# gatorBytes_Sensor_board.net
KiCad netlist of a schematic drawn in EAGLE
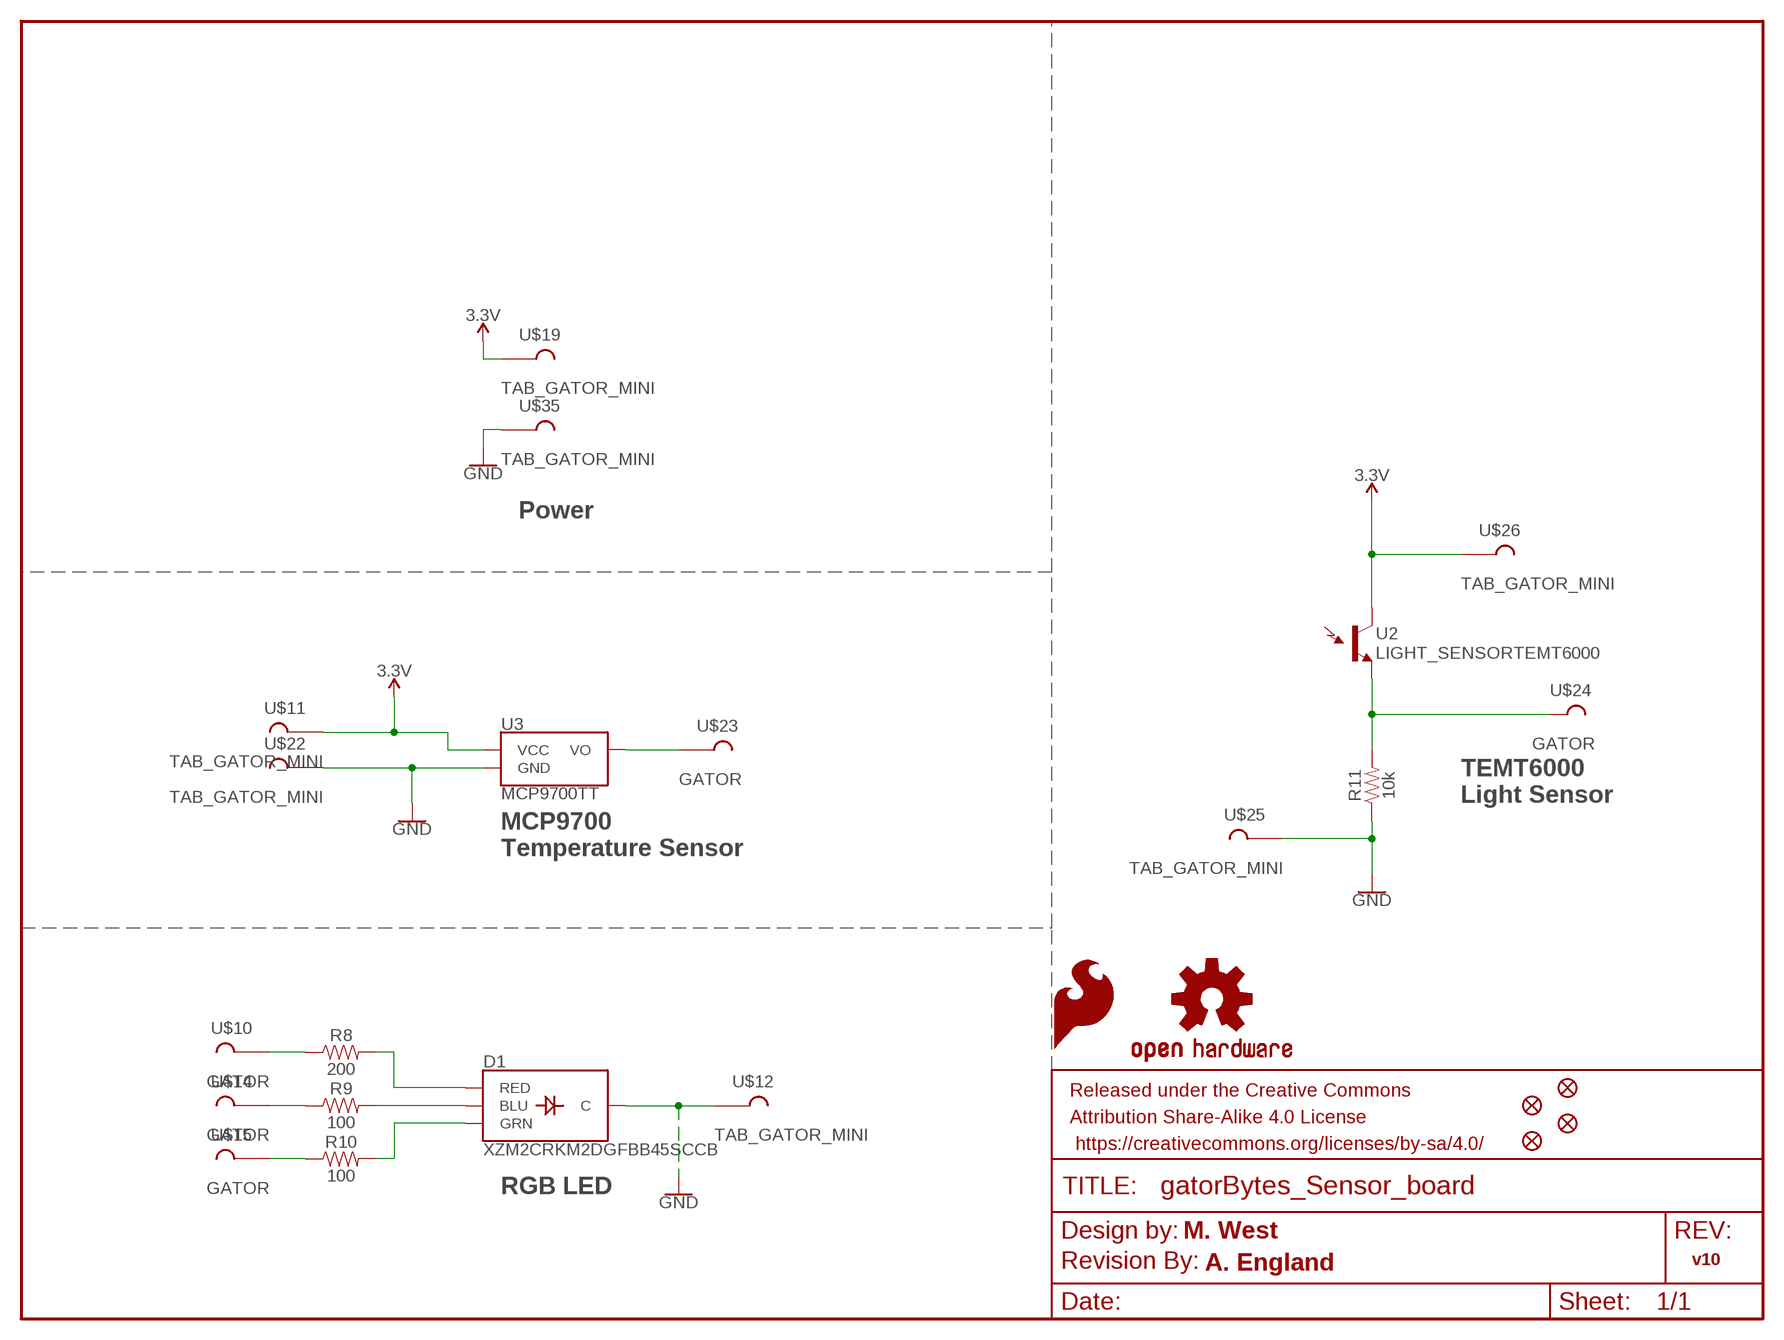
[diagram p0: schematic, sheet 1]

(export (version "E")
  (design (tool "Eeschema 10.0.6"))
  (components
    (comp (ref "D1")
      (value "XZM2CRKM2DGFBB45SCCB")
      (footprint "eagle-import:PLCC4SMDLED")
      (libsource (lib "eagle-import") (part "SUNLEDSMD1"))
    )
    (comp (ref "FD1")
      (value "FIDUCIALUFIDUCIAL")
      (footprint "eagle-import:FIDUCIAL-MICRO")
      (libsource (lib "eagle-import") (part "FIDUCIALUFIDUCIAL"))
    )
    (comp (ref "FD2")
      (value "FIDUCIALUFIDUCIAL")
      (footprint "eagle-import:FIDUCIAL-MICRO")
      (libsource (lib "eagle-import") (part "FIDUCIALUFIDUCIAL"))
    )
    (comp (ref "FD3")
      (value "FIDUCIALUFIDUCIAL")
      (footprint "eagle-import:FIDUCIAL-MICRO")
      (libsource (lib "eagle-import") (part "FIDUCIALUFIDUCIAL"))
    )
    (comp (ref "FD4")
      (value "FIDUCIALUFIDUCIAL")
      (footprint "eagle-import:FIDUCIAL-MICRO")
      (libsource (lib "eagle-import") (part "FIDUCIALUFIDUCIAL"))
    )
    (comp (ref "FRAME1")
      (value "FRAME-LETTER")
      (footprint "eagle-import:CREATIVE_COMMONS")
      (libsource (lib "eagle-import") (part "FRAME-LETTER"))
    )
    (comp (ref "LOGO1")
      (value "SFE_LOGO_FLAME.1_INCH")
      (footprint "eagle-import:SFE_LOGO_FLAME_.1")
      (libsource (lib "eagle-import") (part "SFE_LOGO_FLAME.1_INCH"))
    )
    (comp (ref "LOGO2")
      (value "OSHW-LOGOS")
      (footprint "eagle-import:OSHW-LOGO-S")
      (libsource (lib "eagle-import") (part "OSHW-LOGOS"))
    )
    (comp (ref "LOGO7")
      (value "REVISION")
      (footprint "eagle-import:REVISION")
      (libsource (lib "eagle-import") (part "REVISION"))
    )
    (comp (ref "R8")
      (value "200")
      (footprint "eagle-import:0603")
      (libsource (lib "eagle-import") (part "200OHM-0603-1/10W-1%"))
    )
    (comp (ref "R9")
      (value "100")
      (footprint "eagle-import:0603")
      (libsource (lib "eagle-import") (part "100OHM-0603-1/4W-5%"))
    )
    (comp (ref "R10")
      (value "100")
      (footprint "eagle-import:0603")
      (libsource (lib "eagle-import") (part "100OHM-0603-1/4W-5%"))
    )
    (comp (ref "R11")
      (value "10k")
      (footprint "eagle-import:0603")
      (libsource (lib "eagle-import") (part "10KOHM-0603-1/10W-1%"))
    )
    (comp (ref "U$10")
      (value "GATOR")
      (footprint "eagle-import:GATOR")
      (libsource (lib "eagle-import") (part "GATOR"))
    )
    (comp (ref "U$11")
      (value "TAB_GATOR_MINI")
      (footprint "eagle-import:TAB_GATOR_MINI")
      (libsource (lib "eagle-import") (part "TAB_GATOR_MINI"))
    )
    (comp (ref "U$12")
      (value "TAB_GATOR_MINI")
      (footprint "eagle-import:TAB_GATOR_MINI")
      (libsource (lib "eagle-import") (part "TAB_GATOR_MINI"))
    )
    (comp (ref "U$14")
      (value "GATOR")
      (footprint "eagle-import:GATOR")
      (libsource (lib "eagle-import") (part "GATOR"))
    )
    (comp (ref "U$15")
      (value "GATOR")
      (footprint "eagle-import:GATOR")
      (libsource (lib "eagle-import") (part "GATOR"))
    )
    (comp (ref "U$19")
      (value "TAB_GATOR_MINI")
      (footprint "eagle-import:TAB_GATOR_MINI")
      (libsource (lib "eagle-import") (part "TAB_GATOR_MINI"))
    )
    (comp (ref "U$22")
      (value "TAB_GATOR_MINI")
      (footprint "eagle-import:TAB_GATOR_MINI")
      (libsource (lib "eagle-import") (part "TAB_GATOR_MINI"))
    )
    (comp (ref "U$23")
      (value "GATOR")
      (footprint "eagle-import:GATOR")
      (libsource (lib "eagle-import") (part "GATOR"))
    )
    (comp (ref "U$24")
      (value "GATOR")
      (footprint "eagle-import:GATOR")
      (libsource (lib "eagle-import") (part "GATOR"))
    )
    (comp (ref "U$25")
      (value "TAB_GATOR_MINI")
      (footprint "eagle-import:TAB_GATOR_MINI")
      (libsource (lib "eagle-import") (part "TAB_GATOR_MINI"))
    )
    (comp (ref "U$26")
      (value "TAB_GATOR_MINI")
      (footprint "eagle-import:TAB_GATOR_MINI")
      (libsource (lib "eagle-import") (part "TAB_GATOR_MINI"))
    )
    (comp (ref "U$35")
      (value "TAB_GATOR_MINI")
      (footprint "eagle-import:TAB_GATOR_MINI")
      (libsource (lib "eagle-import") (part "TAB_GATOR_MINI"))
    )
    (comp (ref "U2")
      (value "LIGHT_SENSORTEMT6000")
      (footprint "eagle-import:TEMT6000")
      (libsource (lib "eagle-import") (part "LIGHT_SENSORTEMT6000"))
    )
    (comp (ref "U3")
      (value "MCP9700TT")
      (footprint "eagle-import:SOT23-3")
      (libsource (lib "eagle-import") (part "MCP9700TT"))
    )
  )
  (nets
    (net (code "1") (name "3.3V") (class "Default")
      (node (ref "U$11") (pin "P1") (pinfunction "P$1_P1") (pintype "bidirectional"))
      (node (ref "U$19") (pin "P1") (pinfunction "P$1_P1") (pintype "bidirectional"))
      (node (ref "U$26") (pin "P1") (pinfunction "P$1_P1") (pintype "bidirectional"))
      (node (ref "U2") (pin "COLLECTOR") (pinfunction "C1_COLLECTOR") (pintype "passive"))
      (node (ref "U3") (pin "1") (pinfunction "VCC_1") (pintype "bidirectional"))
    )
    (net (code "2") (name "GND") (class "Default")
      (node (ref "D1") (pin "4") (pinfunction "C_4") (pintype "bidirectional"))
      (node (ref "R11") (pin "1") (pinfunction "1_1") (pintype "passive"))
      (node (ref "U$12") (pin "P1") (pinfunction "P$1_P1") (pintype "bidirectional"))
      (node (ref "U$22") (pin "P1") (pinfunction "P$1_P1") (pintype "bidirectional"))
      (node (ref "U$25") (pin "P1") (pinfunction "P$1_P1") (pintype "bidirectional"))
      (node (ref "U$35") (pin "P1") (pinfunction "P$1_P1") (pintype "bidirectional"))
      (node (ref "U3") (pin "3") (pinfunction "GND_3") (pintype "bidirectional"))
    )
    (net (code "3") (name "Net-(D1-BLU)") (class "Default")
      (node (ref "D1") (pin "3") (pinfunction "BLU_3") (pintype "bidirectional"))
      (node (ref "R9") (pin "2") (pinfunction "2_2") (pintype "passive"))
    )
    (net (code "4") (name "Net-(D1-GRN)") (class "Default")
      (node (ref "D1") (pin "2") (pinfunction "GRN_2") (pintype "bidirectional"))
      (node (ref "R10") (pin "2") (pinfunction "2_2") (pintype "passive"))
    )
    (net (code "5") (name "Net-(D1-RED)") (class "Default")
      (node (ref "D1") (pin "1") (pinfunction "RED_1") (pintype "bidirectional"))
      (node (ref "R8") (pin "2") (pinfunction "2_2") (pintype "passive"))
    )
    (net (code "6") (name "Net-(R8-Pad1)") (class "Default")
      (node (ref "R8") (pin "1") (pinfunction "1_1") (pintype "passive"))
      (node (ref "U$10") (pin "P$1") (pinfunction "P$1_P$1") (pintype "bidirectional"))
      (node (ref "U$10") (pin "P$2") (pinfunction "P$1_P$2") (pintype "bidirectional"))
    )
    (net (code "7") (name "Net-(R9-Pad1)") (class "Default")
      (node (ref "R9") (pin "1") (pinfunction "1_1") (pintype "passive"))
      (node (ref "U$14") (pin "P$1") (pinfunction "P$1_P$1") (pintype "bidirectional"))
      (node (ref "U$14") (pin "P$2") (pinfunction "P$1_P$2") (pintype "bidirectional"))
    )
    (net (code "8") (name "Net-(R10-Pad1)") (class "Default")
      (node (ref "R10") (pin "1") (pinfunction "1_1") (pintype "passive"))
      (node (ref "U$15") (pin "P$1") (pinfunction "P$1_P$1") (pintype "bidirectional"))
      (node (ref "U$15") (pin "P$2") (pinfunction "P$1_P$2") (pintype "bidirectional"))
    )
    (net (code "9") (name "Net-(U2-E1)") (class "Default")
      (node (ref "R11") (pin "2") (pinfunction "2_2") (pintype "passive"))
      (node (ref "U$24") (pin "P$1") (pinfunction "P$1_P$1") (pintype "bidirectional"))
      (node (ref "U$24") (pin "P$2") (pinfunction "P$1_P$2") (pintype "bidirectional"))
      (node (ref "U2") (pin "EMITTER") (pinfunction "E1_EMITTER") (pintype "passive"))
    )
    (net (code "10") (name "Net-(U3-VO)") (class "Default")
      (node (ref "U$23") (pin "P$1") (pinfunction "P$1_P$1") (pintype "bidirectional"))
      (node (ref "U$23") (pin "P$2") (pinfunction "P$1_P$2") (pintype "bidirectional"))
      (node (ref "U3") (pin "2") (pinfunction "VO_2") (pintype "bidirectional"))
    )
  )
)
